# ltk-mw-display_main.net
KiCad netlist of a schematic drawn in Altium Designer
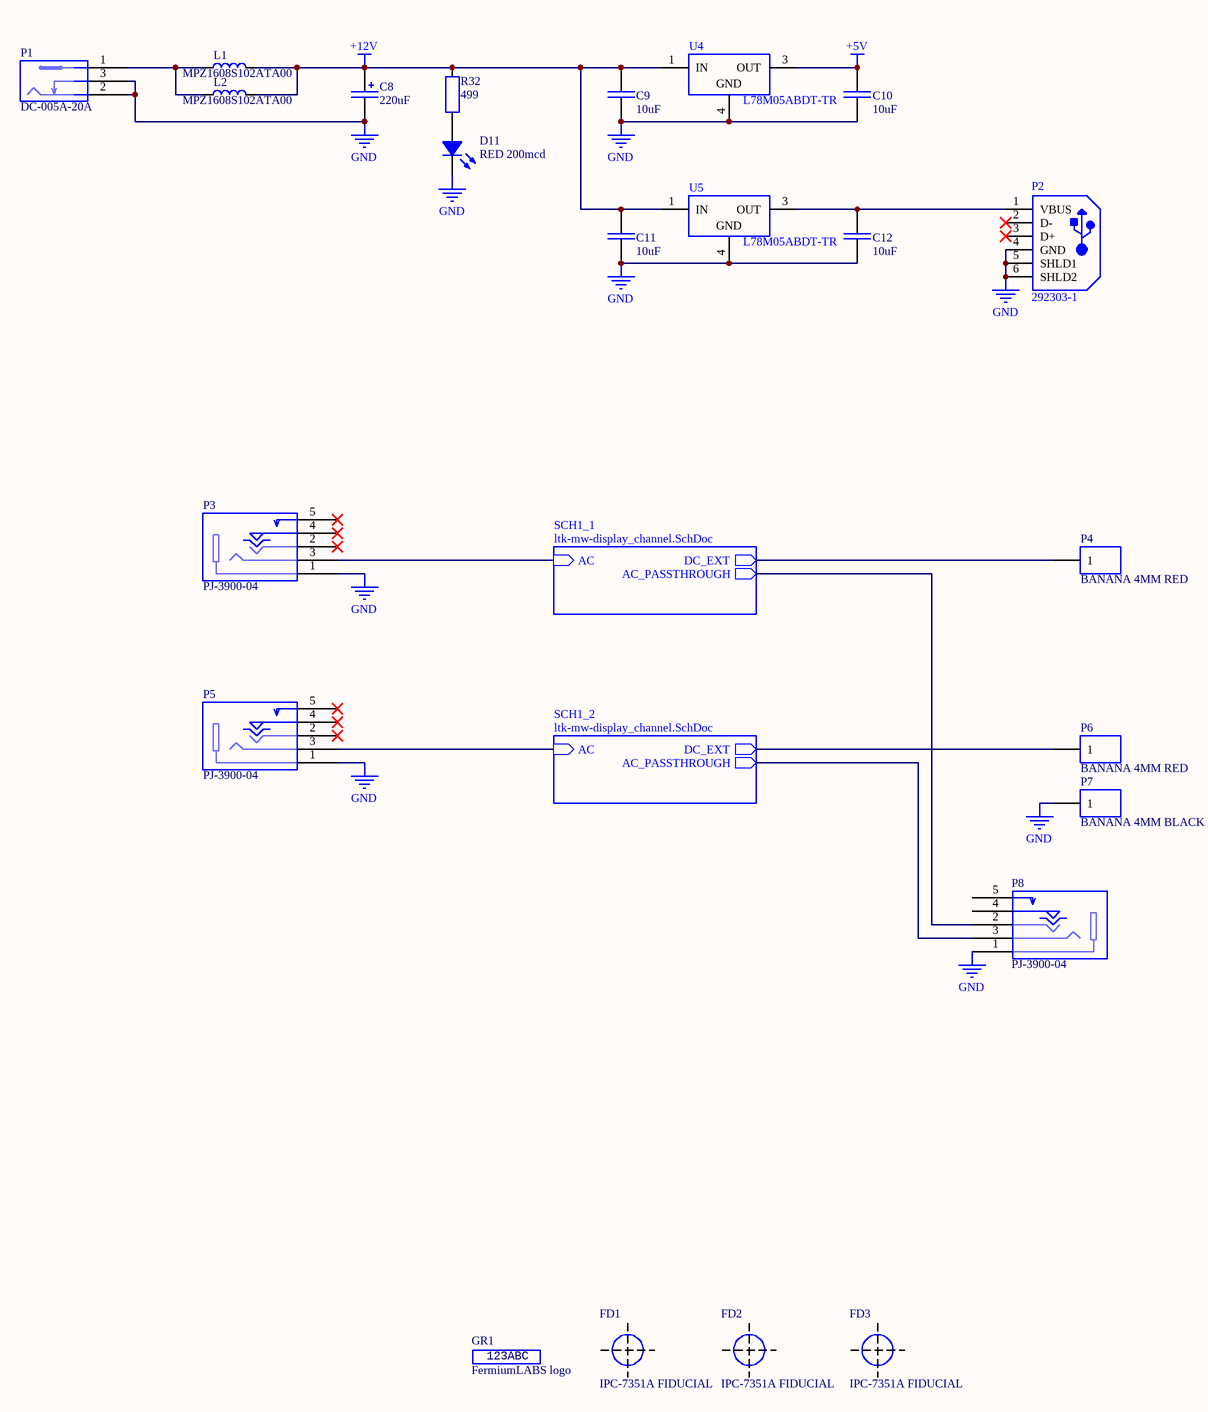
[diagram p0: ltk-mw-display_main.SchDoc]

(export (version "E")
  (design (tool "Eeschema 10.0.6"))
  (components
    (comp (ref "C8")
      (value "220uF")
      (footprint "3924B366-8672-45E9-B0BE-62DACC24E783")
      (description "CAP  THT ELEC 220uF 25V 20%")
      (fields (field (name "PART NUMBER") "1a28df19-6d3e-4a71-836c-f22920f8e8ab"))
      (libsource (lib "frmdblib") (part "GENERIC_C_ELEC"))
    )
    (comp (ref "C9")
      (value "10uF")
      (footprint "CAP 0805_2012")
      (description "CAP SMD MLCC 10uF 25V 0805 X5R")
      (fields (field (name "PART NUMBER") "1ffbe5a9-0884-4740-bdad-20a6a98400e6"))
      (libsource (lib "frmdblib") (part "GENERIC_C"))
    )
    (comp (ref "C10")
      (value "10uF")
      (footprint "CAP 0805_2012")
      (description "CAP SMD MLCC 10uF 25V 0805 X5R")
      (fields (field (name "PART NUMBER") "1ffbe5a9-0884-4740-bdad-20a6a98400e6"))
      (libsource (lib "frmdblib") (part "GENERIC_C"))
    )
    (comp (ref "C11")
      (value "10uF")
      (footprint "CAP 0805_2012")
      (description "CAP SMD MLCC 10uF 25V 0805 X5R")
      (fields (field (name "PART NUMBER") "1ffbe5a9-0884-4740-bdad-20a6a98400e6"))
      (libsource (lib "frmdblib") (part "GENERIC_C"))
    )
    (comp (ref "C12")
      (value "10uF")
      (footprint "CAP 0805_2012")
      (description "CAP SMD MLCC 10uF 25V 0805 X5R")
      (fields (field (name "PART NUMBER") "1ffbe5a9-0884-4740-bdad-20a6a98400e6"))
      (libsource (lib "frmdblib") (part "GENERIC_C"))
    )
    (comp (ref "D11")
      (value "RED 200mcd")
      (footprint "ED49B4F6-595F-4D62-96BB-D7184CAA9B94")
      (description "DIODE LED THT 5MM RED 200mcd")
      (fields (field (name "PART NUMBER") "c65ae3d2-9539-4634-8979-616a331b7494"))
      (libsource (lib "frmdblib") (part "GENERIC_D_LED"))
    )
    (comp (ref "FD1")
      (value "IPC-7351A FIDUCIAL")
      (footprint "FIDUCIAL-IPC-7351A")
      (description "GRAPHICS FIDUCIAL IPC-7351A")
      (fields (field (name "PART NUMBER") "19da4612-eb95-43bb-9984-553a52b2a224"))
      (libsource (lib "frmdblib") (part "GENERIC_FIDUCIAL"))
    )
    (comp (ref "FD2")
      (value "IPC-7351A FIDUCIAL")
      (footprint "FIDUCIAL-IPC-7351A")
      (description "GRAPHICS FIDUCIAL IPC-7351A")
      (fields (field (name "PART NUMBER") "19da4612-eb95-43bb-9984-553a52b2a224"))
      (libsource (lib "frmdblib") (part "GENERIC_FIDUCIAL"))
    )
    (comp (ref "FD3")
      (value "IPC-7351A FIDUCIAL")
      (footprint "FIDUCIAL-IPC-7351A")
      (description "GRAPHICS FIDUCIAL IPC-7351A")
      (fields (field (name "PART NUMBER") "19da4612-eb95-43bb-9984-553a52b2a224"))
      (libsource (lib "frmdblib") (part "GENERIC_FIDUCIAL"))
    )
    (comp (ref "GR1")
      (value "FermiumLABS logo")
      (footprint "5394DE47-A0E8-4329-8464-7791B7C19310")
      (description "GRAPHICS LOGO FERMIUM LABS SRL")
      (fields (field (name "PART NUMBER") "50f8ea88-0034-49fe-a263-d8e97bc35e2f"))
      (libsource (lib "frmdblib") (part "GENERIC_GRAPHIC"))
    )
    (comp (ref "L1")
      (value "MPZ1608S102ATA00")
      (footprint "FER 0603_1608")
      (description "FER SMD CHIP 0603 800mA 1K@100MHz 300mOhm")
      (fields (field (name "PART NUMBER") "a4b2e015-bf25-47b8-954c-a5b040744a3a"))
      (libsource (lib "frmdblib") (part "GENERIC_L"))
    )
    (comp (ref "L2")
      (value "MPZ1608S102ATA00")
      (footprint "FER 0603_1608")
      (description "FER SMD CHIP 0603 800mA 1K@100MHz 300mOhm")
      (fields (field (name "PART NUMBER") "a4b2e015-bf25-47b8-954c-a5b040744a3a"))
      (libsource (lib "frmdblib") (part "GENERIC_L"))
    )
    (comp (ref "P1")
      (value "DC-005A-20A")
      (footprint "F0972D8A-C5C0-4A84-836D-A9666EE65C2D")
      (description "CONN THT DC JACK 0.5A 30VDC 5Kcycles")
      (fields (field (name "PART NUMBER") "b53db51a-1725-412b-9039-fa7a45c7c438"))
      (libsource (lib "frmdblib") (part "34A1CD0B-E262-46EF-B9F1-39CB809C308F"))
    )
    (comp (ref "P2")
      (value "292303-1")
      (footprint "8A51F738-712D-4EE5-9D6B-BB16603F834E")
      (description "CONN THT USB TYPE-A HIGH RELIABILITY")
      (fields (field (name "PART NUMBER") "9ff2a560-e541-4da0-adda-013cc9c65511"))
      (libsource (lib "frmdblib") (part "19C864C6-9E55-4731-863D-CE3C8E5D2E63"))
    )
    (comp (ref "P3")
      (value "PJ-3900-04")
      (footprint "7EF2B92C-0FC9-4C85-B662-5CEC65BFCCC4")
      (description "CONN THT 3.5mm AUDIO STEREO AUX SWITCH")
      (fields (field (name "PART NUMBER") "80507a24-5d7c-4cf5-953e-f54832d54564"))
      (libsource (lib "frmdblib") (part "46E41D2F-79BD-46AC-B778-70B2D50A946A"))
    )
    (comp (ref "P4")
      (value "BANANA 4MM RED")
      (footprint "2382AA2C-2335-4562-94C7-3B9045982126")
      (description "CONN BANANA SOCKET 4MM RED")
      (fields (field (name "PART NUMBER") "3b84d3c9-1de5-4004-b768-3958a778153b"))
      (libsource (lib "frmdblib") (part "Header 1"))
    )
    (comp (ref "P5")
      (value "PJ-3900-04")
      (footprint "7EF2B92C-0FC9-4C85-B662-5CEC65BFCCC4")
      (description "CONN THT 3.5mm AUDIO STEREO AUX SWITCH")
      (fields (field (name "PART NUMBER") "80507a24-5d7c-4cf5-953e-f54832d54564"))
      (libsource (lib "frmdblib") (part "46E41D2F-79BD-46AC-B778-70B2D50A946A"))
    )
    (comp (ref "P6")
      (value "BANANA 4MM RED")
      (footprint "2382AA2C-2335-4562-94C7-3B9045982126")
      (description "CONN BANANA SOCKET 4MM RED")
      (fields (field (name "PART NUMBER") "3b84d3c9-1de5-4004-b768-3958a778153b"))
      (libsource (lib "frmdblib") (part "Header 1"))
    )
    (comp (ref "P7")
      (value "BANANA 4MM BLACK")
      (footprint "2382AA2C-2335-4562-94C7-3B9045982126")
      (description "CONN BANANA SOCKET 4MM BLACK")
      (fields (field (name "PART NUMBER") "80ef162c-aaff-440a-80ad-5900ce15f9c1"))
      (libsource (lib "frmdblib") (part "Header 1"))
    )
    (comp (ref "P8")
      (value "PJ-3900-04")
      (footprint "7EF2B92C-0FC9-4C85-B662-5CEC65BFCCC4")
      (description "CONN THT 3.5mm AUDIO STEREO AUX SWITCH")
      (fields (field (name "PART NUMBER") "80507a24-5d7c-4cf5-953e-f54832d54564"))
      (libsource (lib "") (part "46E41D2F-79BD-46AC-B778-70B2D50A946A_1"))
    )
    (comp (ref "R32")
      (value "499")
      (footprint "RES 1206_3216")
      (description "RES SMD 499 OHM 1% 1/4W 1206")
      (fields (field (name "PART NUMBER") "c8bf8de8-3430-48dd-94ac-a027709c0c4f"))
      (libsource (lib "frmdblib") (part "GENERIC_R"))
    )
    (comp (ref "U4")
      (value "L78M05ABDT-TR")
      (footprint "4BDA507D-BB70-4009-B963-85AD90086B51")
      (description "IC SMD LINEAR VOLTAGE REGULATOR 5V 500mA DPAK/TO-252")
      (fields (field (name "PART NUMBER") "446536aa-1bdd-4764-8cae-49f4e0c126ff"))
      (libsource (lib "frmdblib") (part "568C7F7F-B71D-457E-B5FB-AE9D42DA8928"))
    )
    (comp (ref "U5")
      (value "L78M05ABDT-TR")
      (footprint "4BDA507D-BB70-4009-B963-85AD90086B51")
      (description "IC SMD LINEAR VOLTAGE REGULATOR 5V 500mA DPAK/TO-252")
      (fields (field (name "PART NUMBER") "446536aa-1bdd-4764-8cae-49f4e0c126ff"))
      (libsource (lib "frmdblib") (part "568C7F7F-B71D-457E-B5FB-AE9D42DA8928"))
    )
  )
  (nets
    (net (code "1") (name "+5V") (class "Default")
      (node (ref "C10") (pin "1") (pintype "passive"))
      (node (ref "U4") (pin "3") (pinfunction "OUT_3") (pintype "power_in"))
    )
    (net (code "2") (name "+12V") (class "Default")
      (node (ref "C11") (pin "1") (pintype "passive"))
      (node (ref "C8") (pin "1") (pintype "passive"))
      (node (ref "C9") (pin "1") (pintype "passive"))
      (node (ref "L1") (pin "2") (pintype "passive"))
      (node (ref "L2") (pin "2") (pintype "passive"))
      (node (ref "R32") (pin "2") (pintype "passive"))
      (node (ref "U4") (pin "1") (pinfunction "IN_1") (pintype "power_in"))
      (node (ref "U5") (pin "1") (pinfunction "IN_1") (pintype "power_in"))
    )
    (net (code "3") (name "/AC") (class "Default")
      (node (ref "P5") (pin "3") (pinfunction "L_3") (pintype "passive"))
    )
    (net (code "4") (name "/AC_1") (class "Default")
      (node (ref "P3") (pin "3") (pinfunction "L_3") (pintype "passive"))
    )
    (net (code "5") (name "/AC_PASSTHROUGH") (class "Default")
      (node (ref "P8") (pin "3") (pinfunction "L_3") (pintype "passive"))
    )
    (net (code "6") (name "/AC_PASSTHROUGH_1") (class "Default")
      (node (ref "P8") (pin "2") (pinfunction "R_2") (pintype "passive"))
    )
    (net (code "7") (name "/DC_EXT") (class "Default")
      (node (ref "P6") (pin "1") (pinfunction "1_1") (pintype "passive"))
    )
    (net (code "8") (name "/DC_EXT_1") (class "Default")
      (node (ref "P4") (pin "1") (pinfunction "1_1") (pintype "passive"))
    )
    (net (code "9") (name "GND") (class "Default")
      (node (ref "C10") (pin "2") (pintype "passive"))
      (node (ref "C11") (pin "2") (pintype "passive"))
      (node (ref "C12") (pin "2") (pintype "passive"))
      (node (ref "C8") (pin "2") (pintype "passive"))
      (node (ref "C9") (pin "2") (pintype "passive"))
      (node (ref "D11") (pin "1") (pinfunction "K_1") (pintype "passive"))
      (node (ref "P1") (pin "2") (pinfunction "2_2") (pintype "passive"))
      (node (ref "P1") (pin "3") (pinfunction "3_3") (pintype "passive"))
      (node (ref "P2") (pin "4") (pinfunction "GND_4") (pintype "passive"))
      (node (ref "P2") (pin "5") (pinfunction "SHLD1_5") (pintype "passive"))
      (node (ref "P2") (pin "6") (pinfunction "SHLD2_6") (pintype "passive"))
      (node (ref "P3") (pin "1") (pinfunction "GND_1") (pintype "passive"))
      (node (ref "P5") (pin "1") (pinfunction "GND_1") (pintype "passive"))
      (node (ref "P7") (pin "1") (pinfunction "1_1") (pintype "passive"))
      (node (ref "P8") (pin "1") (pinfunction "GND_1") (pintype "passive"))
      (node (ref "U4") (pin "4") (pinfunction "GND_4") (pintype "power_in"))
      (node (ref "U5") (pin "4") (pinfunction "GND_4") (pintype "power_in"))
    )
    (net (code "10") (name "Net-(D11-A)") (class "Default")
      (node (ref "D11") (pin "2") (pinfunction "A_2") (pintype "passive"))
      (node (ref "R32") (pin "1") (pintype "passive"))
    )
    (net (code "11") (name "Net-(L1-Pad1)") (class "Default")
      (node (ref "L1") (pin "1") (pintype "passive"))
      (node (ref "L2") (pin "1") (pintype "passive"))
      (node (ref "P1") (pin "1") (pinfunction "1_1") (pintype "passive"))
    )
    (net (code "12") (name "Net-(P2-VBUS)") (class "Default")
      (node (ref "C12") (pin "1") (pintype "passive"))
      (node (ref "P2") (pin "1") (pinfunction "VBUS_1") (pintype "passive"))
      (node (ref "U5") (pin "3") (pinfunction "OUT_3") (pintype "power_in"))
    )
    (net (code "13") (name "unconnected-(P2-D+-Pad3)") (class "Default")
      (node (ref "P2") (pin "3") (pinfunction "D+_3") (pintype "passive+no_connect"))
    )
    (net (code "14") (name "unconnected-(P2-D--Pad2)") (class "Default")
      (node (ref "P2") (pin "2") (pinfunction "D-_2") (pintype "passive+no_connect"))
    )
    (net (code "15") (name "unconnected-(P3-AUX-Pad4)") (class "Default")
      (node (ref "P3") (pin "4") (pinfunction "AUX_4") (pintype "passive+no_connect"))
    )
    (net (code "16") (name "unconnected-(P3-AUX-Pad5)") (class "Default")
      (node (ref "P3") (pin "5") (pinfunction "AUX_5") (pintype "passive+no_connect"))
    )
    (net (code "17") (name "unconnected-(P3-R-Pad2)") (class "Default")
      (node (ref "P3") (pin "2") (pinfunction "R_2") (pintype "passive+no_connect"))
    )
    (net (code "18") (name "unconnected-(P5-AUX-Pad4)") (class "Default")
      (node (ref "P5") (pin "4") (pinfunction "AUX_4") (pintype "passive+no_connect"))
    )
    (net (code "19") (name "unconnected-(P5-AUX-Pad5)") (class "Default")
      (node (ref "P5") (pin "5") (pinfunction "AUX_5") (pintype "passive+no_connect"))
    )
    (net (code "20") (name "unconnected-(P5-R-Pad2)") (class "Default")
      (node (ref "P5") (pin "2") (pinfunction "R_2") (pintype "passive+no_connect"))
    )
    (net (code "21") (name "unconnected-(P8-AUX-Pad4)") (class "Default")
      (node (ref "P8") (pin "4") (pinfunction "AUX_4") (pintype "passive"))
    )
    (net (code "22") (name "unconnected-(P8-AUX-Pad5)") (class "Default")
      (node (ref "P8") (pin "5") (pinfunction "AUX_5") (pintype "passive"))
    )
  )
)
